# hirose_omnetics_adapter_schematic_rev4.net
KiCad netlist of a schematic drawn in EAGLE
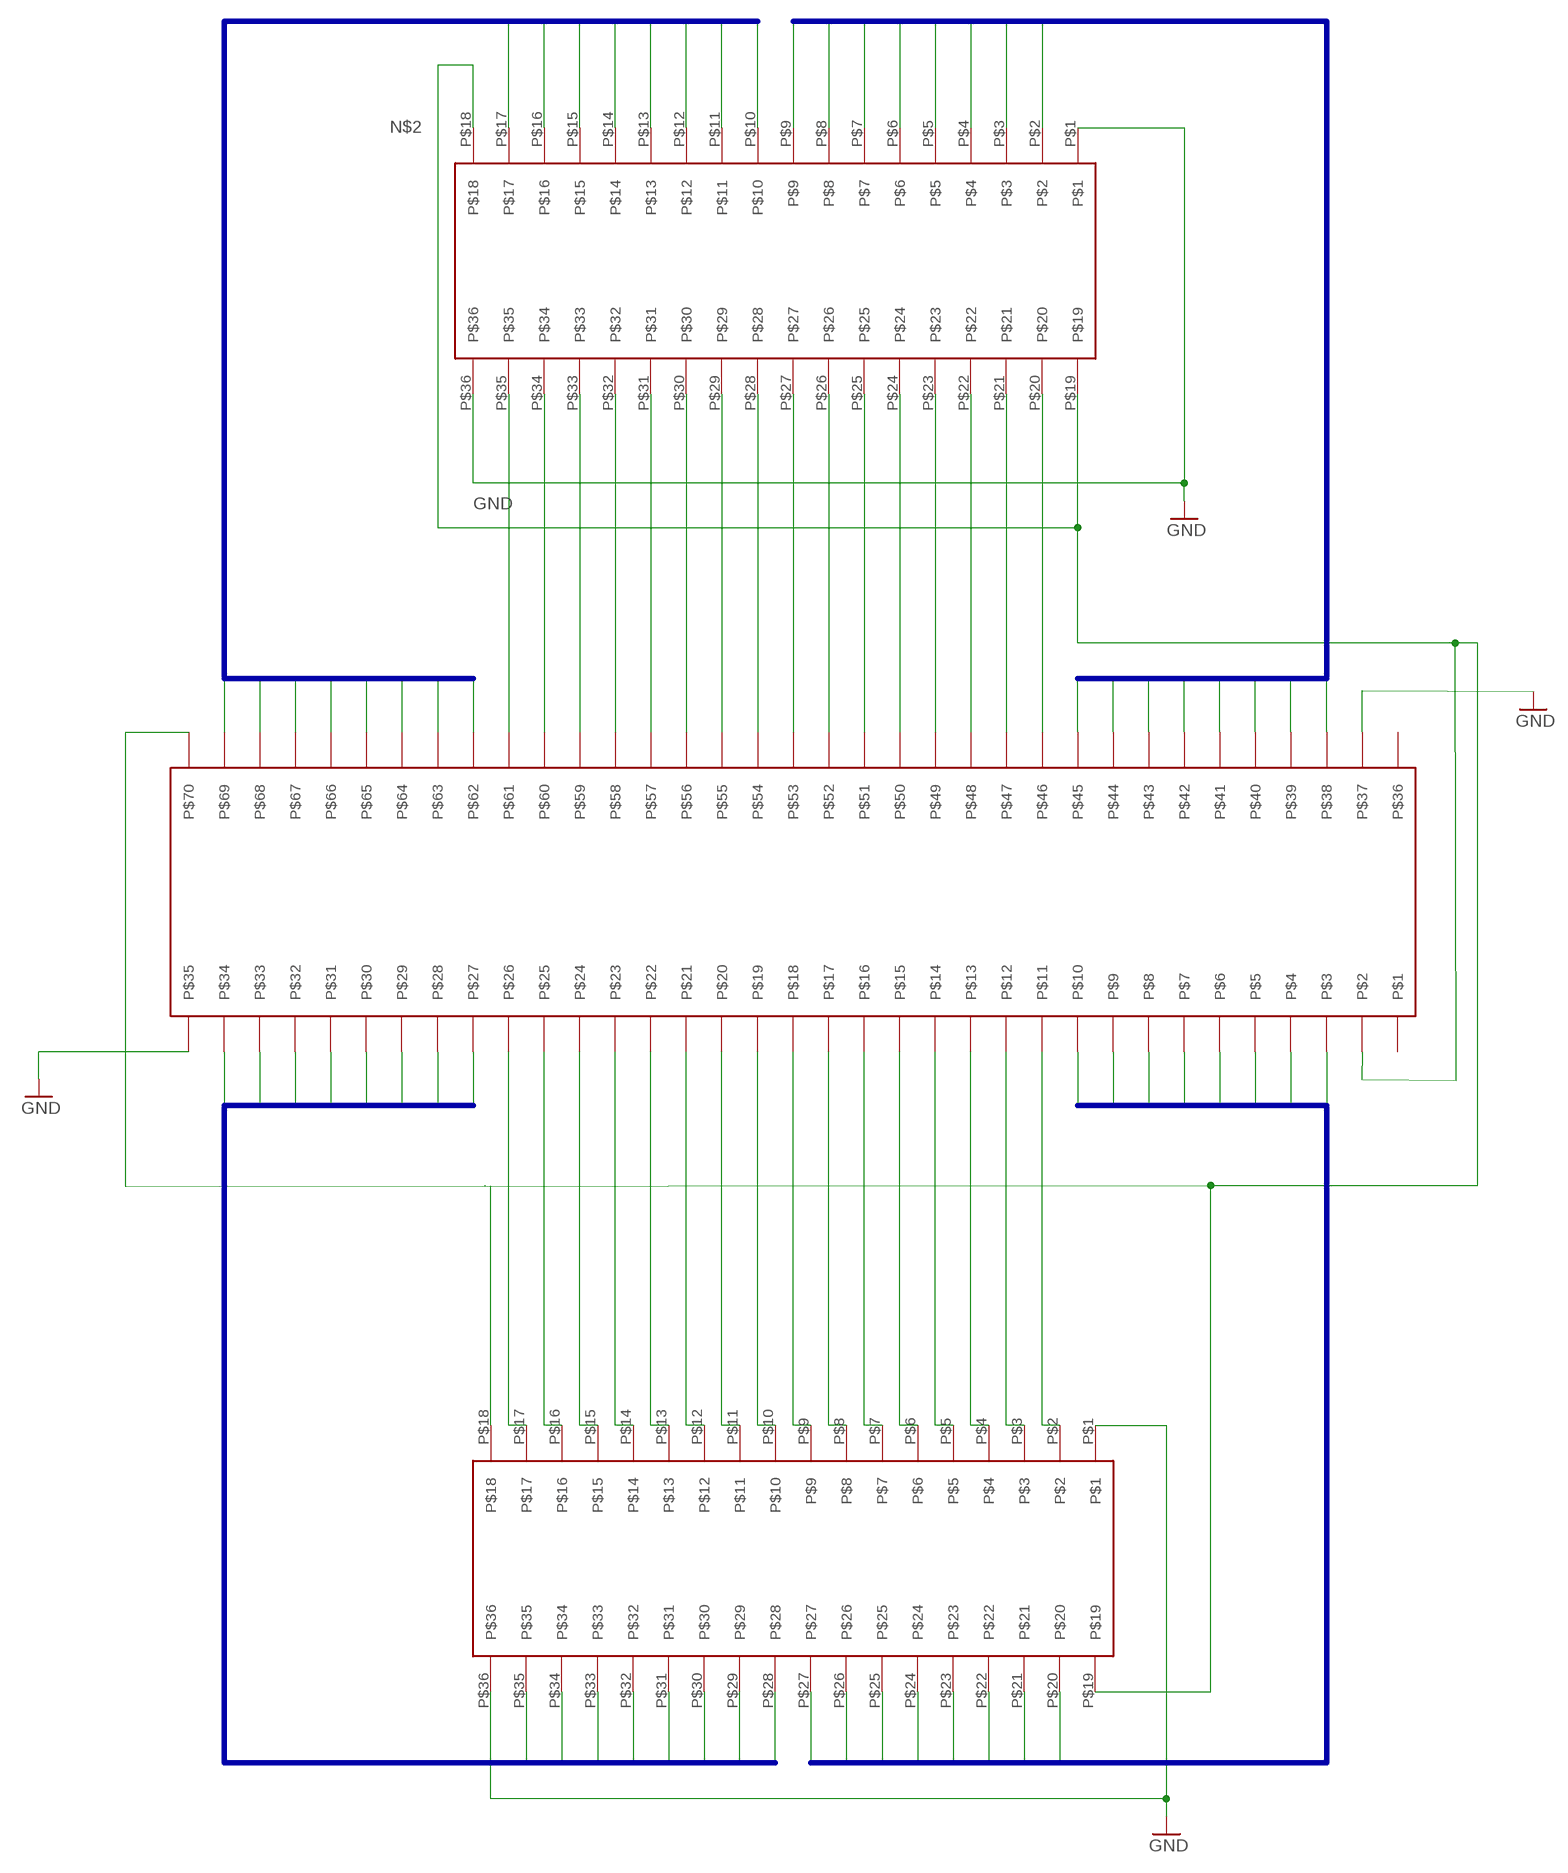
[diagram p0: schematic, sheet 1]

(export (version "E")
  (design (tool "Eeschema 10.0.6"))
  (components
    (comp (ref "U$1")
      (value "HIROSE_DF40_70PIN")
      (footprint "eagle-import:HIROSE_DF40C-70DS")
      (libsource (lib "eagle-import") (part "HIROSE_DF40_70PIN"))
    )
    (comp (ref "U$2")
      (value "OMNETICS_A79026")
      (footprint "eagle-import:OMNETICS_A79026-001")
      (libsource (lib "eagle-import") (part "OMNETICS_A79026"))
    )
    (comp (ref "U$3")
      (value "OMNETICS_A79026")
      (footprint "eagle-import:OMNETICS_A79026-001")
      (libsource (lib "eagle-import") (part "OMNETICS_A79026"))
    )
  )
  (nets
    (net (code "1") (name "/A0") (class "Default")
      (node (ref "U$1") (pin "P$62") (pinfunction "P$62_P$62") (pintype "bidirectional"))
      (node (ref "U$2") (pin "P$10") (pinfunction "P$10_P$10") (pintype "bidirectional"))
    )
    (net (code "2") (name "/A1") (class "Default")
      (node (ref "U$1") (pin "P$63") (pinfunction "P$63_P$63") (pintype "bidirectional"))
      (node (ref "U$2") (pin "P$11") (pinfunction "P$11_P$11") (pintype "bidirectional"))
    )
    (net (code "3") (name "/A2") (class "Default")
      (node (ref "U$1") (pin "P$64") (pinfunction "P$64_P$64") (pintype "bidirectional"))
      (node (ref "U$2") (pin "P$12") (pinfunction "P$12_P$12") (pintype "bidirectional"))
    )
    (net (code "4") (name "/A3") (class "Default")
      (node (ref "U$1") (pin "P$65") (pinfunction "P$65_P$65") (pintype "bidirectional"))
      (node (ref "U$2") (pin "P$13") (pinfunction "P$13_P$13") (pintype "bidirectional"))
    )
    (net (code "5") (name "/A4") (class "Default")
      (node (ref "U$1") (pin "P$66") (pinfunction "P$66_P$66") (pintype "bidirectional"))
      (node (ref "U$2") (pin "P$14") (pinfunction "P$14_P$14") (pintype "bidirectional"))
    )
    (net (code "6") (name "/A5") (class "Default")
      (node (ref "U$1") (pin "P$67") (pinfunction "P$67_P$67") (pintype "bidirectional"))
      (node (ref "U$2") (pin "P$15") (pinfunction "P$15_P$15") (pintype "bidirectional"))
    )
    (net (code "7") (name "/A6") (class "Default")
      (node (ref "U$1") (pin "P$68") (pinfunction "P$68_P$68") (pintype "bidirectional"))
      (node (ref "U$2") (pin "P$16") (pinfunction "P$16_P$16") (pintype "bidirectional"))
    )
    (net (code "8") (name "/A7") (class "Default")
      (node (ref "U$1") (pin "P$69") (pinfunction "P$69_P$69") (pintype "bidirectional"))
      (node (ref "U$2") (pin "P$17") (pinfunction "P$17_P$17") (pintype "bidirectional"))
    )
    (net (code "9") (name "/B0") (class "Default")
      (node (ref "U$1") (pin "P$45") (pinfunction "P$45_P$45") (pintype "bidirectional"))
      (node (ref "U$2") (pin "P$9") (pinfunction "P$9_P$9") (pintype "bidirectional"))
    )
    (net (code "10") (name "/B1") (class "Default")
      (node (ref "U$1") (pin "P$44") (pinfunction "P$44_P$44") (pintype "bidirectional"))
      (node (ref "U$2") (pin "P$8") (pinfunction "P$8_P$8") (pintype "bidirectional"))
    )
    (net (code "11") (name "/B2") (class "Default")
      (node (ref "U$1") (pin "P$43") (pinfunction "P$43_P$43") (pintype "bidirectional"))
      (node (ref "U$2") (pin "P$7") (pinfunction "P$7_P$7") (pintype "bidirectional"))
    )
    (net (code "12") (name "/B3") (class "Default")
      (node (ref "U$1") (pin "P$42") (pinfunction "P$42_P$42") (pintype "bidirectional"))
      (node (ref "U$2") (pin "P$6") (pinfunction "P$6_P$6") (pintype "bidirectional"))
    )
    (net (code "13") (name "/B4") (class "Default")
      (node (ref "U$1") (pin "P$41") (pinfunction "P$41_P$41") (pintype "bidirectional"))
      (node (ref "U$2") (pin "P$5") (pinfunction "P$5_P$5") (pintype "bidirectional"))
    )
    (net (code "14") (name "/B5") (class "Default")
      (node (ref "U$1") (pin "P$40") (pinfunction "P$40_P$40") (pintype "bidirectional"))
      (node (ref "U$2") (pin "P$4") (pinfunction "P$4_P$4") (pintype "bidirectional"))
    )
    (net (code "15") (name "/B6") (class "Default")
      (node (ref "U$1") (pin "P$39") (pinfunction "P$39_P$39") (pintype "bidirectional"))
      (node (ref "U$2") (pin "P$3") (pinfunction "P$3_P$3") (pintype "bidirectional"))
    )
    (net (code "16") (name "/B7") (class "Default")
      (node (ref "U$1") (pin "P$38") (pinfunction "P$38_P$38") (pintype "bidirectional"))
      (node (ref "U$2") (pin "P$2") (pinfunction "P$2_P$2") (pintype "bidirectional"))
    )
    (net (code "17") (name "/C0") (class "Default")
      (node (ref "U$1") (pin "P$27") (pinfunction "P$27_P$27") (pintype "bidirectional"))
      (node (ref "U$3") (pin "P$28") (pinfunction "P$28_P$28") (pintype "bidirectional"))
    )
    (net (code "18") (name "/C1") (class "Default")
      (node (ref "U$1") (pin "P$28") (pinfunction "P$28_P$28") (pintype "bidirectional"))
      (node (ref "U$3") (pin "P$29") (pinfunction "P$29_P$29") (pintype "bidirectional"))
    )
    (net (code "19") (name "/C2") (class "Default")
      (node (ref "U$1") (pin "P$29") (pinfunction "P$29_P$29") (pintype "bidirectional"))
      (node (ref "U$3") (pin "P$30") (pinfunction "P$30_P$30") (pintype "bidirectional"))
    )
    (net (code "20") (name "/C3") (class "Default")
      (node (ref "U$1") (pin "P$30") (pinfunction "P$30_P$30") (pintype "bidirectional"))
      (node (ref "U$3") (pin "P$31") (pinfunction "P$31_P$31") (pintype "bidirectional"))
    )
    (net (code "21") (name "/C4") (class "Default")
      (node (ref "U$1") (pin "P$31") (pinfunction "P$31_P$31") (pintype "bidirectional"))
      (node (ref "U$3") (pin "P$32") (pinfunction "P$32_P$32") (pintype "bidirectional"))
    )
    (net (code "22") (name "/C5") (class "Default")
      (node (ref "U$1") (pin "P$32") (pinfunction "P$32_P$32") (pintype "bidirectional"))
      (node (ref "U$3") (pin "P$33") (pinfunction "P$33_P$33") (pintype "bidirectional"))
    )
    (net (code "23") (name "/C6") (class "Default")
      (node (ref "U$1") (pin "P$33") (pinfunction "P$33_P$33") (pintype "bidirectional"))
      (node (ref "U$3") (pin "P$34") (pinfunction "P$34_P$34") (pintype "bidirectional"))
    )
    (net (code "24") (name "/C7") (class "Default")
      (node (ref "U$1") (pin "P$34") (pinfunction "P$34_P$34") (pintype "bidirectional"))
      (node (ref "U$3") (pin "P$35") (pinfunction "P$35_P$35") (pintype "bidirectional"))
    )
    (net (code "25") (name "/D0") (class "Default")
      (node (ref "U$1") (pin "P$10") (pinfunction "P$10_P$10") (pintype "bidirectional"))
      (node (ref "U$3") (pin "P$27") (pinfunction "P$27_P$27") (pintype "bidirectional"))
    )
    (net (code "26") (name "/D1") (class "Default")
      (node (ref "U$1") (pin "P$9") (pinfunction "P$9_P$9") (pintype "bidirectional"))
      (node (ref "U$3") (pin "P$26") (pinfunction "P$26_P$26") (pintype "bidirectional"))
    )
    (net (code "27") (name "/D2") (class "Default")
      (node (ref "U$1") (pin "P$8") (pinfunction "P$8_P$8") (pintype "bidirectional"))
      (node (ref "U$3") (pin "P$25") (pinfunction "P$25_P$25") (pintype "bidirectional"))
    )
    (net (code "28") (name "/D3") (class "Default")
      (node (ref "U$1") (pin "P$7") (pinfunction "P$7_P$7") (pintype "bidirectional"))
      (node (ref "U$3") (pin "P$24") (pinfunction "P$24_P$24") (pintype "bidirectional"))
    )
    (net (code "29") (name "/D4") (class "Default")
      (node (ref "U$1") (pin "P$6") (pinfunction "P$6_P$6") (pintype "bidirectional"))
      (node (ref "U$3") (pin "P$23") (pinfunction "P$23_P$23") (pintype "bidirectional"))
    )
    (net (code "30") (name "/D5") (class "Default")
      (node (ref "U$1") (pin "P$5") (pinfunction "P$5_P$5") (pintype "bidirectional"))
      (node (ref "U$3") (pin "P$22") (pinfunction "P$22_P$22") (pintype "bidirectional"))
    )
    (net (code "31") (name "/D6") (class "Default")
      (node (ref "U$1") (pin "P$4") (pinfunction "P$4_P$4") (pintype "bidirectional"))
      (node (ref "U$3") (pin "P$21") (pinfunction "P$21_P$21") (pintype "bidirectional"))
    )
    (net (code "32") (name "/D7") (class "Default")
      (node (ref "U$1") (pin "P$3") (pinfunction "P$3_P$3") (pintype "bidirectional"))
      (node (ref "U$3") (pin "P$20") (pinfunction "P$20_P$20") (pintype "bidirectional"))
    )
    (net (code "33") (name "/N$2") (class "Default")
      (node (ref "U$1") (pin "P$2") (pinfunction "P$2_P$2") (pintype "bidirectional"))
      (node (ref "U$1") (pin "P$70") (pinfunction "P$70_P$70") (pintype "bidirectional"))
      (node (ref "U$2") (pin "P$18") (pinfunction "P$18_P$18") (pintype "bidirectional"))
      (node (ref "U$2") (pin "P$19") (pinfunction "P$19_P$19") (pintype "bidirectional"))
      (node (ref "U$3") (pin "P$18") (pinfunction "P$18_P$18") (pintype "bidirectional"))
      (node (ref "U$3") (pin "P$19") (pinfunction "P$19_P$19") (pintype "bidirectional"))
    )
    (net (code "34") (name "GND") (class "Default")
      (node (ref "U$1") (pin "P$35") (pinfunction "P$35_P$35") (pintype "bidirectional"))
      (node (ref "U$1") (pin "P$37") (pinfunction "P$37_P$37") (pintype "bidirectional"))
      (node (ref "U$2") (pin "P$1") (pinfunction "P$1_P$1") (pintype "bidirectional"))
      (node (ref "U$2") (pin "P$36") (pinfunction "P$36_P$36") (pintype "bidirectional"))
      (node (ref "U$3") (pin "P$1") (pinfunction "P$1_P$1") (pintype "bidirectional"))
      (node (ref "U$3") (pin "P$36") (pinfunction "P$36_P$36") (pintype "bidirectional"))
    )
    (net (code "35") (name "Net-(U$1-PadP$11)") (class "Default")
      (node (ref "U$1") (pin "P$11") (pinfunction "P$11_P$11") (pintype "bidirectional"))
      (node (ref "U$3") (pin "P$2") (pinfunction "P$2_P$2") (pintype "bidirectional"))
    )
    (net (code "36") (name "Net-(U$1-PadP$12)") (class "Default")
      (node (ref "U$1") (pin "P$12") (pinfunction "P$12_P$12") (pintype "bidirectional"))
      (node (ref "U$3") (pin "P$3") (pinfunction "P$3_P$3") (pintype "bidirectional"))
    )
    (net (code "37") (name "Net-(U$1-PadP$13)") (class "Default")
      (node (ref "U$1") (pin "P$13") (pinfunction "P$13_P$13") (pintype "bidirectional"))
      (node (ref "U$3") (pin "P$4") (pinfunction "P$4_P$4") (pintype "bidirectional"))
    )
    (net (code "38") (name "Net-(U$1-PadP$14)") (class "Default")
      (node (ref "U$1") (pin "P$14") (pinfunction "P$14_P$14") (pintype "bidirectional"))
      (node (ref "U$3") (pin "P$5") (pinfunction "P$5_P$5") (pintype "bidirectional"))
    )
    (net (code "39") (name "Net-(U$1-PadP$15)") (class "Default")
      (node (ref "U$1") (pin "P$15") (pinfunction "P$15_P$15") (pintype "bidirectional"))
      (node (ref "U$3") (pin "P$6") (pinfunction "P$6_P$6") (pintype "bidirectional"))
    )
    (net (code "40") (name "Net-(U$1-PadP$16)") (class "Default")
      (node (ref "U$1") (pin "P$16") (pinfunction "P$16_P$16") (pintype "bidirectional"))
      (node (ref "U$3") (pin "P$7") (pinfunction "P$7_P$7") (pintype "bidirectional"))
    )
    (net (code "41") (name "Net-(U$1-PadP$17)") (class "Default")
      (node (ref "U$1") (pin "P$17") (pinfunction "P$17_P$17") (pintype "bidirectional"))
      (node (ref "U$3") (pin "P$8") (pinfunction "P$8_P$8") (pintype "bidirectional"))
    )
    (net (code "42") (name "Net-(U$1-PadP$18)") (class "Default")
      (node (ref "U$1") (pin "P$18") (pinfunction "P$18_P$18") (pintype "bidirectional"))
      (node (ref "U$3") (pin "P$9") (pinfunction "P$9_P$9") (pintype "bidirectional"))
    )
    (net (code "43") (name "Net-(U$1-PadP$19)") (class "Default")
      (node (ref "U$1") (pin "P$19") (pinfunction "P$19_P$19") (pintype "bidirectional"))
      (node (ref "U$3") (pin "P$10") (pinfunction "P$10_P$10") (pintype "bidirectional"))
    )
    (net (code "44") (name "Net-(U$1-PadP$20)") (class "Default")
      (node (ref "U$1") (pin "P$20") (pinfunction "P$20_P$20") (pintype "bidirectional"))
      (node (ref "U$3") (pin "P$11") (pinfunction "P$11_P$11") (pintype "bidirectional"))
    )
    (net (code "45") (name "Net-(U$1-PadP$21)") (class "Default")
      (node (ref "U$1") (pin "P$21") (pinfunction "P$21_P$21") (pintype "bidirectional"))
      (node (ref "U$3") (pin "P$12") (pinfunction "P$12_P$12") (pintype "bidirectional"))
    )
    (net (code "46") (name "Net-(U$1-PadP$22)") (class "Default")
      (node (ref "U$1") (pin "P$22") (pinfunction "P$22_P$22") (pintype "bidirectional"))
      (node (ref "U$3") (pin "P$13") (pinfunction "P$13_P$13") (pintype "bidirectional"))
    )
    (net (code "47") (name "Net-(U$1-PadP$23)") (class "Default")
      (node (ref "U$1") (pin "P$23") (pinfunction "P$23_P$23") (pintype "bidirectional"))
      (node (ref "U$3") (pin "P$14") (pinfunction "P$14_P$14") (pintype "bidirectional"))
    )
    (net (code "48") (name "Net-(U$1-PadP$24)") (class "Default")
      (node (ref "U$1") (pin "P$24") (pinfunction "P$24_P$24") (pintype "bidirectional"))
      (node (ref "U$3") (pin "P$15") (pinfunction "P$15_P$15") (pintype "bidirectional"))
    )
    (net (code "49") (name "Net-(U$1-PadP$25)") (class "Default")
      (node (ref "U$1") (pin "P$25") (pinfunction "P$25_P$25") (pintype "bidirectional"))
      (node (ref "U$3") (pin "P$16") (pinfunction "P$16_P$16") (pintype "bidirectional"))
    )
    (net (code "50") (name "Net-(U$1-PadP$26)") (class "Default")
      (node (ref "U$1") (pin "P$26") (pinfunction "P$26_P$26") (pintype "bidirectional"))
      (node (ref "U$3") (pin "P$17") (pinfunction "P$17_P$17") (pintype "bidirectional"))
    )
    (net (code "51") (name "Net-(U$1-PadP$46)") (class "Default")
      (node (ref "U$1") (pin "P$46") (pinfunction "P$46_P$46") (pintype "bidirectional"))
      (node (ref "U$2") (pin "P$20") (pinfunction "P$20_P$20") (pintype "bidirectional"))
    )
    (net (code "52") (name "Net-(U$1-PadP$47)") (class "Default")
      (node (ref "U$1") (pin "P$47") (pinfunction "P$47_P$47") (pintype "bidirectional"))
      (node (ref "U$2") (pin "P$21") (pinfunction "P$21_P$21") (pintype "bidirectional"))
    )
    (net (code "53") (name "Net-(U$1-PadP$48)") (class "Default")
      (node (ref "U$1") (pin "P$48") (pinfunction "P$48_P$48") (pintype "bidirectional"))
      (node (ref "U$2") (pin "P$22") (pinfunction "P$22_P$22") (pintype "bidirectional"))
    )
    (net (code "54") (name "Net-(U$1-PadP$49)") (class "Default")
      (node (ref "U$1") (pin "P$49") (pinfunction "P$49_P$49") (pintype "bidirectional"))
      (node (ref "U$2") (pin "P$23") (pinfunction "P$23_P$23") (pintype "bidirectional"))
    )
    (net (code "55") (name "Net-(U$1-PadP$50)") (class "Default")
      (node (ref "U$1") (pin "P$50") (pinfunction "P$50_P$50") (pintype "bidirectional"))
      (node (ref "U$2") (pin "P$24") (pinfunction "P$24_P$24") (pintype "bidirectional"))
    )
    (net (code "56") (name "Net-(U$1-PadP$51)") (class "Default")
      (node (ref "U$1") (pin "P$51") (pinfunction "P$51_P$51") (pintype "bidirectional"))
      (node (ref "U$2") (pin "P$25") (pinfunction "P$25_P$25") (pintype "bidirectional"))
    )
    (net (code "57") (name "Net-(U$1-PadP$52)") (class "Default")
      (node (ref "U$1") (pin "P$52") (pinfunction "P$52_P$52") (pintype "bidirectional"))
      (node (ref "U$2") (pin "P$26") (pinfunction "P$26_P$26") (pintype "bidirectional"))
    )
    (net (code "58") (name "Net-(U$1-PadP$53)") (class "Default")
      (node (ref "U$1") (pin "P$53") (pinfunction "P$53_P$53") (pintype "bidirectional"))
      (node (ref "U$2") (pin "P$27") (pinfunction "P$27_P$27") (pintype "bidirectional"))
    )
    (net (code "59") (name "Net-(U$1-PadP$54)") (class "Default")
      (node (ref "U$1") (pin "P$54") (pinfunction "P$54_P$54") (pintype "bidirectional"))
      (node (ref "U$2") (pin "P$28") (pinfunction "P$28_P$28") (pintype "bidirectional"))
    )
    (net (code "60") (name "Net-(U$1-PadP$55)") (class "Default")
      (node (ref "U$1") (pin "P$55") (pinfunction "P$55_P$55") (pintype "bidirectional"))
      (node (ref "U$2") (pin "P$29") (pinfunction "P$29_P$29") (pintype "bidirectional"))
    )
    (net (code "61") (name "Net-(U$1-PadP$56)") (class "Default")
      (node (ref "U$1") (pin "P$56") (pinfunction "P$56_P$56") (pintype "bidirectional"))
      (node (ref "U$2") (pin "P$30") (pinfunction "P$30_P$30") (pintype "bidirectional"))
    )
    (net (code "62") (name "Net-(U$1-PadP$57)") (class "Default")
      (node (ref "U$1") (pin "P$57") (pinfunction "P$57_P$57") (pintype "bidirectional"))
      (node (ref "U$2") (pin "P$31") (pinfunction "P$31_P$31") (pintype "bidirectional"))
    )
    (net (code "63") (name "Net-(U$1-PadP$58)") (class "Default")
      (node (ref "U$1") (pin "P$58") (pinfunction "P$58_P$58") (pintype "bidirectional"))
      (node (ref "U$2") (pin "P$32") (pinfunction "P$32_P$32") (pintype "bidirectional"))
    )
    (net (code "64") (name "Net-(U$1-PadP$59)") (class "Default")
      (node (ref "U$1") (pin "P$59") (pinfunction "P$59_P$59") (pintype "bidirectional"))
      (node (ref "U$2") (pin "P$33") (pinfunction "P$33_P$33") (pintype "bidirectional"))
    )
    (net (code "65") (name "Net-(U$1-PadP$60)") (class "Default")
      (node (ref "U$1") (pin "P$60") (pinfunction "P$60_P$60") (pintype "bidirectional"))
      (node (ref "U$2") (pin "P$34") (pinfunction "P$34_P$34") (pintype "bidirectional"))
    )
    (net (code "66") (name "Net-(U$1-PadP$61)") (class "Default")
      (node (ref "U$1") (pin "P$61") (pinfunction "P$61_P$61") (pintype "bidirectional"))
      (node (ref "U$2") (pin "P$35") (pinfunction "P$35_P$35") (pintype "bidirectional"))
    )
    (net (code "67") (name "unconnected-(U$1-PadP$1)") (class "Default")
      (node (ref "U$1") (pin "P$1") (pinfunction "P$1_P$1") (pintype "bidirectional"))
    )
    (net (code "68") (name "unconnected-(U$1-PadP$36)") (class "Default")
      (node (ref "U$1") (pin "P$36") (pinfunction "P$36_P$36") (pintype "bidirectional"))
    )
  )
)
